# dc_dc_sepic_12-12.net
KiCad netlist of a schematic drawn in Altium Designer
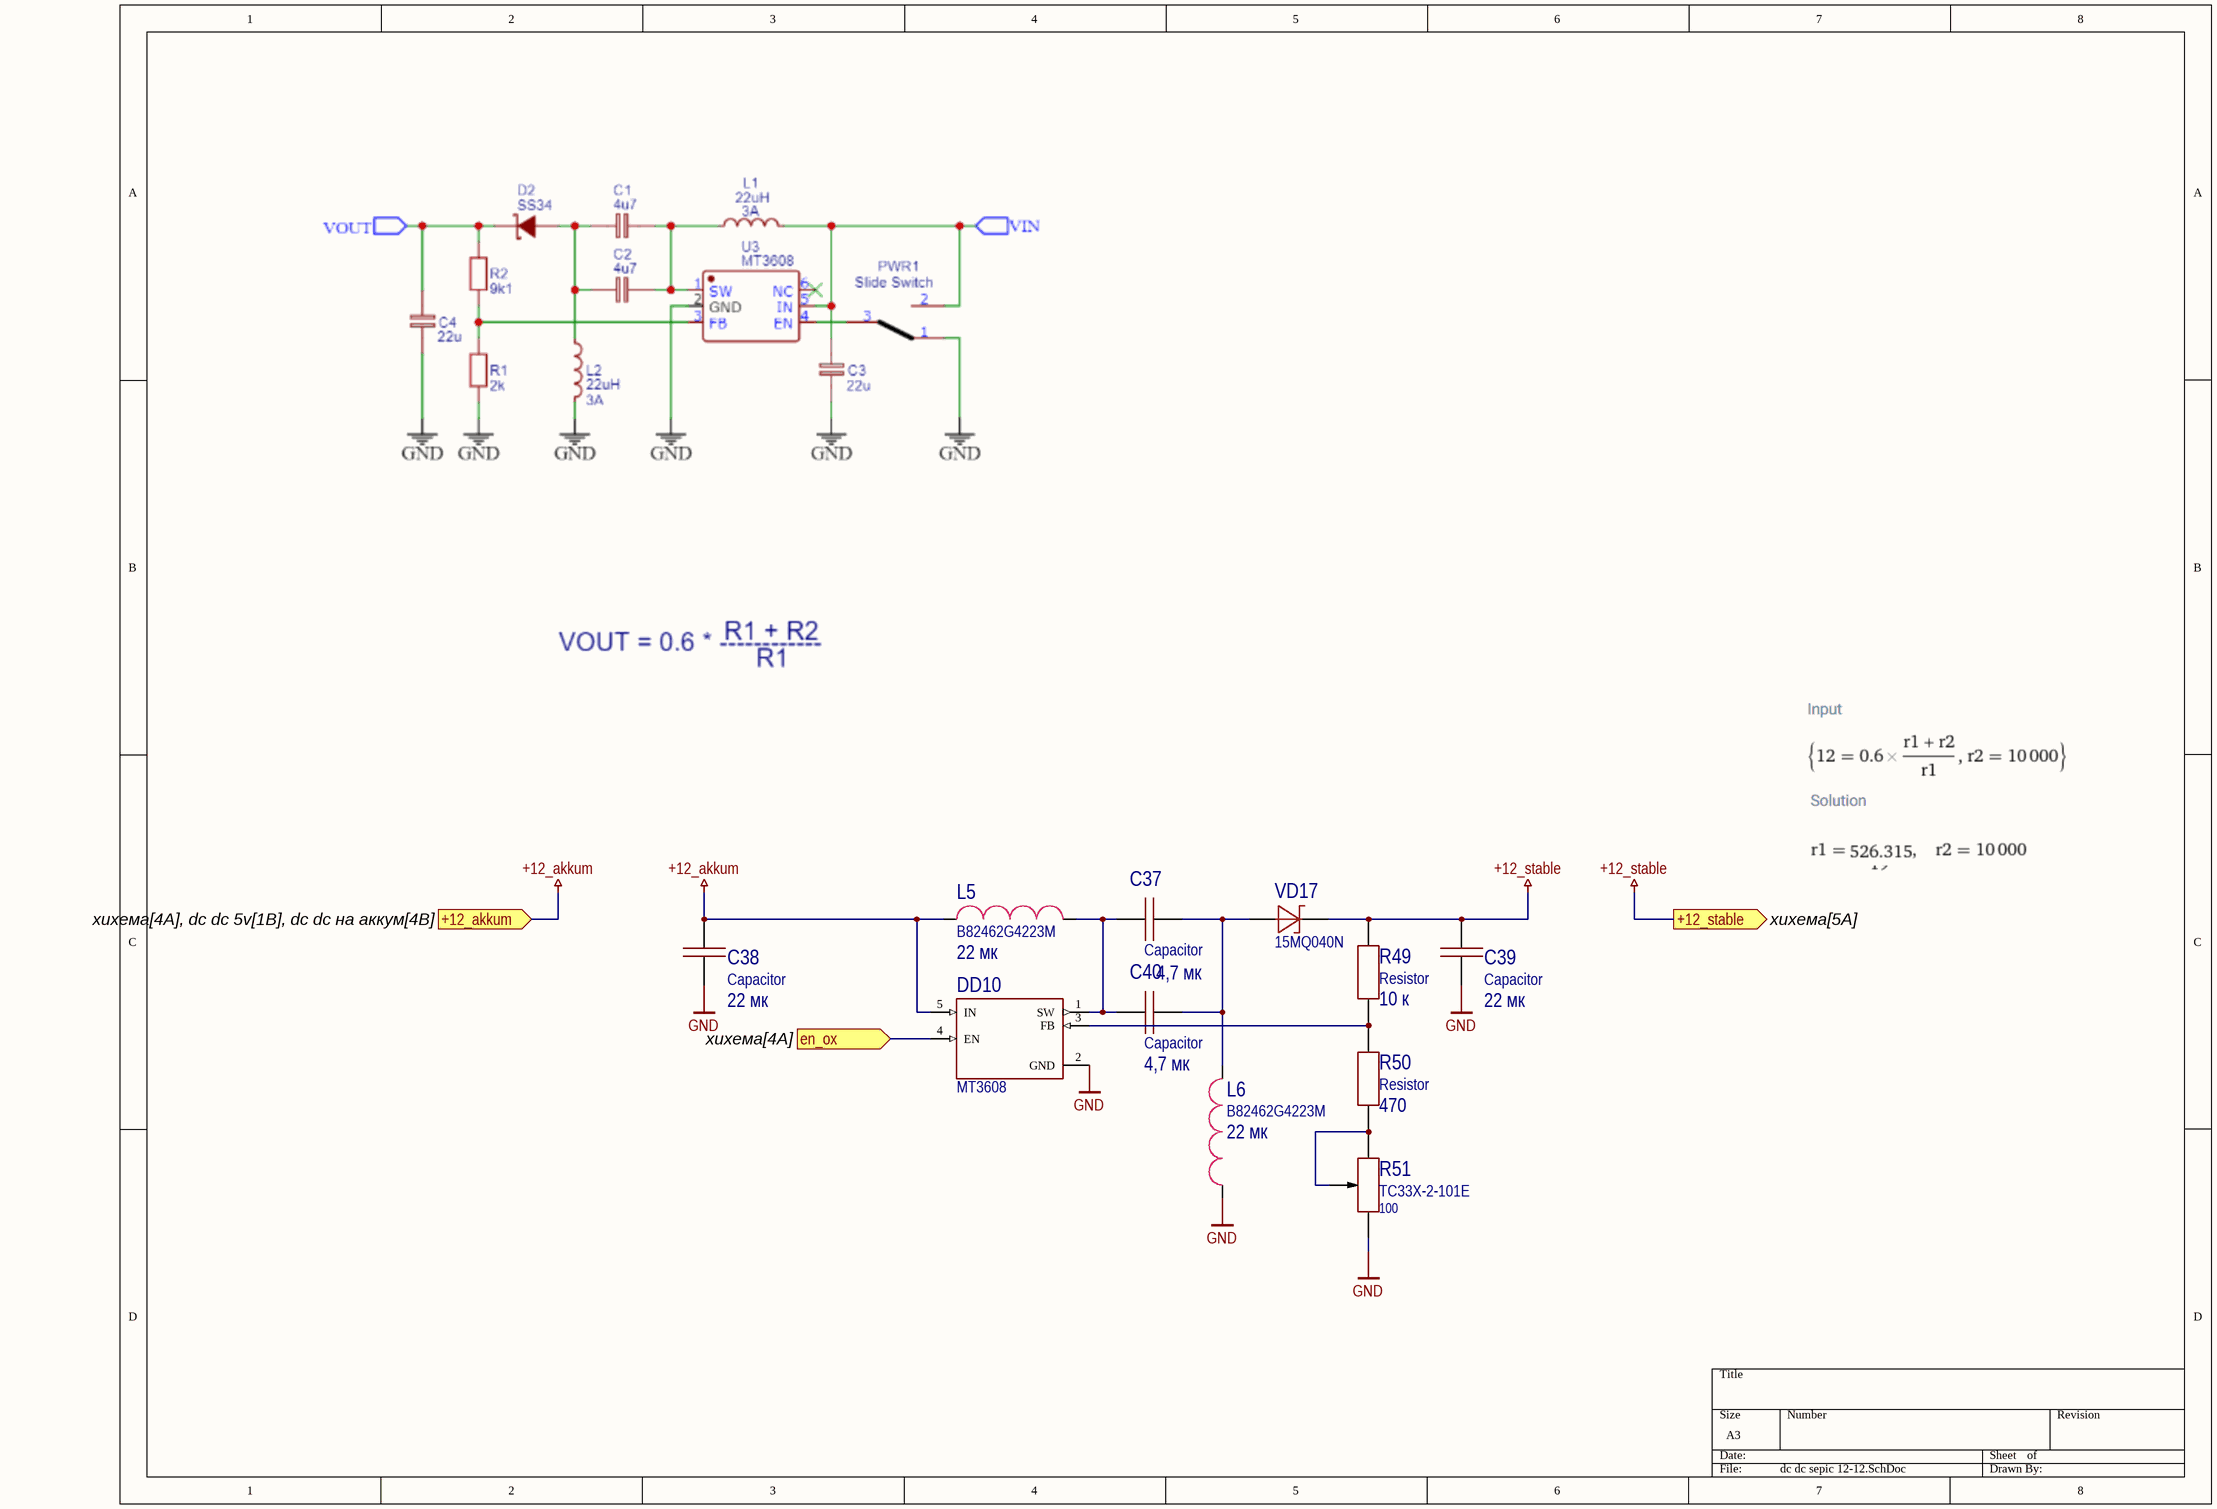
[diagram p0: dc dc sepic 12-12.SchDoc]

(export (version "E")
  (design (tool "Eeschema 10.0.6"))
  (components
    (comp (ref "C37")
      (value "Capacitor")
      (footprint "1206C")
      (description "Конденсатор")
      (fields
        (field (name "ALTIUM_VALUE") "4,7 мк")
        (field (name "PART NUMBER") "Capacitor_4,7u_10_50V_X7R_1206C")
        (field (name "TOLERANCE") "0,1")
      )
      (libsource (lib "Hydrolib") (part "Capacitor"))
    )
    (comp (ref "C38")
      (value "Capacitor")
      (footprint "1210C")
      (description "Конденсатор")
      (fields
        (field (name "ALTIUM_VALUE") "22 мк")
        (field (name "PART NUMBER") "Capacitor_22u_10_25V_X7R_1210C")
        (field (name "TOLERANCE") "0,1")
      )
      (libsource (lib "Hydrolib") (part "Capacitor"))
    )
    (comp (ref "C39")
      (value "Capacitor")
      (footprint "1210C")
      (description "Конденсатор")
      (fields
        (field (name "ALTIUM_VALUE") "22 мк")
        (field (name "PART NUMBER") "Capacitor_22u_10_25V_X7R_1210C")
        (field (name "TOLERANCE") "0,1")
      )
      (libsource (lib "Hydrolib") (part "Capacitor"))
    )
    (comp (ref "C40")
      (value "Capacitor")
      (footprint "1206C")
      (description "Конденсатор")
      (fields
        (field (name "ALTIUM_VALUE") "4,7 мк")
        (field (name "PART NUMBER") "Capacitor_4,7u_10_50V_X7R_1206C")
        (field (name "TOLERANCE") "0,1")
      )
      (libsource (lib "Hydrolib") (part "Capacitor"))
    )
    (comp (ref "DD10")
      (value "MT3608")
      (footprint "SOT23-6")
      (description "Повышающий/SEPIC DC-DC преобразователь 2А 1.2МГц")
      (libsource (lib "Hydrolib") (part "MT3608"))
    )
    (comp (ref "L5")
      (value "B82462G4223M")
      (footprint "B82462G4")
      (description "ЧИП-индуктивность 22мкГн, 1.05A, ±20% катушка")
      (fields (field (name "ALTIUM_VALUE") "22 мк"))
      (libsource (lib "Hydrolib") (part "Inductance"))
    )
    (comp (ref "L6")
      (value "B82462G4223M")
      (footprint "B82462G4")
      (description "ЧИП-индуктивность 22мкГн, 1.05A, ±20% катушка")
      (fields (field (name "ALTIUM_VALUE") "22 мк"))
      (libsource (lib "Hydrolib") (part "Inductance"))
    )
    (comp (ref "R49")
      (value "Resistor")
      (footprint "0603R")
      (description "Резистор номиналом 10 кОм и точностью 1%")
      (fields
        (field (name "ALTIUM_VALUE") "10 к")
        (field (name "PART NUMBER") "Resistor_10k_1_0603")
        (field (name "TOLERANCE") "1%")
      )
      (libsource (lib "Hydrolib") (part "Resistor"))
    )
    (comp (ref "R50")
      (value "Resistor")
      (footprint "0603R")
      (description "Резистор номиналом 470 Ом и точностью 1%")
      (fields
        (field (name "ALTIUM_VALUE") "470")
        (field (name "PART NUMBER") "Resistor_470_1_0603")
        (field (name "TOLERANCE") "1%")
      )
      (libsource (lib "Hydrolib") (part "Resistor"))
    )
    (comp (ref "R51")
      (value "TC33X-2-101E")
      (footprint "3mm_trim")
      (description "Потенциометр керметный 100 Ом 0.1Вт для поверхностного монтажа")
      (fields (field (name "ALTIUM_VALUE") "100") (field (name "TOLERANCE") "50%"))
      (libsource (lib "Hydrolib") (part "trim_res"))
    )
    (comp (ref "VD17")
      (value "15MQ040N")
      (footprint "SMA")
      (description "Диод шоттки на 40 В, ном. ток 2.1 А")
      (libsource (lib "Hydrolib") (part "Schottky_diode"))
    )
  )
  (nets
    (net (code "1") (name "+12_akkum") (class "Default")
      (node (ref "C38") (pin "2") (pinfunction "2_2") (pintype "passive"))
      (node (ref "DD10") (pin "5") (pinfunction "IN_5") (pintype "input"))
      (node (ref "L5") (pin "1") (pinfunction "1_1") (pintype "passive"))
    )
    (net (code "2") (name "+12_stable") (class "Default")
      (node (ref "C39") (pin "2") (pinfunction "2_2") (pintype "passive"))
      (node (ref "R49") (pin "2") (pinfunction "2_2") (pintype "passive"))
      (node (ref "VD17") (pin "2") (pinfunction "2_2") (pintype "passive"))
    )
    (net (code "3") (name "/en_ox") (class "Default")
      (node (ref "DD10") (pin "4") (pinfunction "EN_4") (pintype "input"))
    )
    (net (code "4") (name "GND") (class "Default")
      (node (ref "C38") (pin "1") (pinfunction "1_1") (pintype "passive"))
      (node (ref "C39") (pin "1") (pinfunction "1_1") (pintype "passive"))
      (node (ref "DD10") (pin "2") (pinfunction "GND_2") (pintype "power_in"))
      (node (ref "L6") (pin "1") (pinfunction "1_1") (pintype "passive"))
      (node (ref "R51") (pin "1") (pinfunction "1_1") (pintype "passive"))
    )
    (net (code "5") (name "Net-(C37-Pad2)") (class "Default")
      (node (ref "C37") (pin "2") (pinfunction "2_2") (pintype "passive"))
      (node (ref "C40") (pin "2") (pinfunction "2_2") (pintype "passive"))
      (node (ref "L6") (pin "2") (pinfunction "2_2") (pintype "passive"))
      (node (ref "VD17") (pin "1") (pinfunction "1_1") (pintype "passive"))
    )
    (net (code "6") (name "Net-(DD10-FB)") (class "Default")
      (node (ref "DD10") (pin "3") (pinfunction "FB_3") (pintype "input"))
      (node (ref "R49") (pin "1") (pinfunction "1_1") (pintype "passive"))
      (node (ref "R50") (pin "2") (pinfunction "2_2") (pintype "passive"))
    )
    (net (code "7") (name "Net-(DD10-SW)") (class "Default")
      (node (ref "C37") (pin "1") (pinfunction "1_1") (pintype "passive"))
      (node (ref "C40") (pin "1") (pinfunction "1_1") (pintype "passive"))
      (node (ref "DD10") (pin "1") (pinfunction "SW_1") (pintype "output"))
      (node (ref "L5") (pin "2") (pinfunction "2_2") (pintype "passive"))
    )
    (net (code "8") (name "Net-(R50-Pad1)") (class "Default")
      (node (ref "R50") (pin "1") (pinfunction "1_1") (pintype "passive"))
      (node (ref "R51") (pin "2") (pinfunction "2_2") (pintype "passive"))
      (node (ref "R51") (pin "3") (pinfunction "3_3") (pintype "passive"))
    )
  )
)
